# IRQF401RCT6.net
KiCad netlist of a schematic drawn in EAGLE
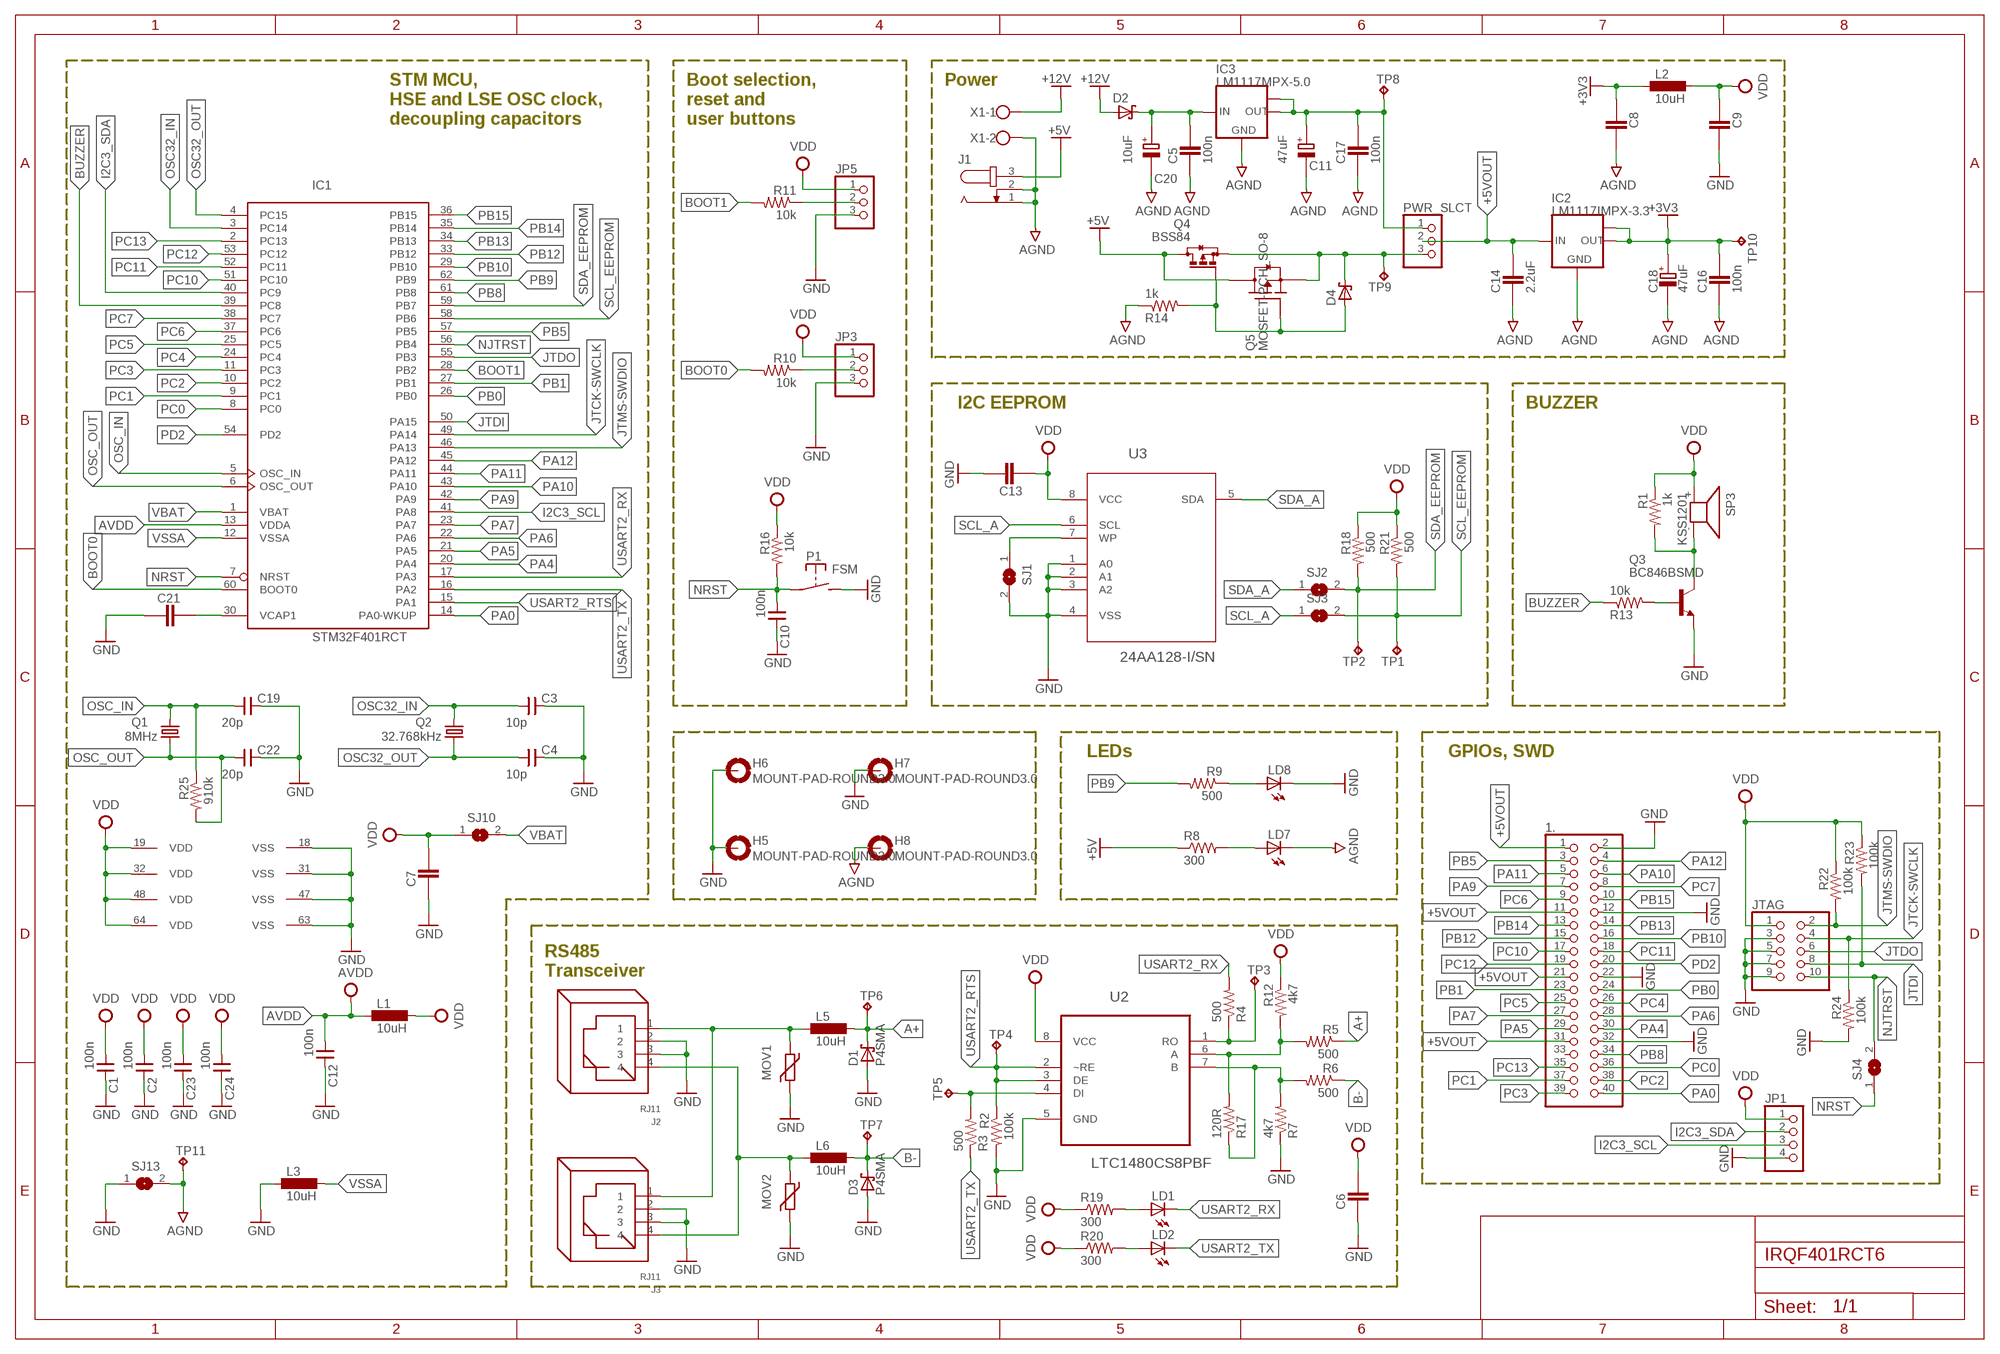
[diagram p0: schematic, sheet 1]

(export (version "E")
  (design (tool "Eeschema 10.0.6"))
  (components
    (comp (ref "1.")
      (value "PINHD-2X20")
      (footprint "eagle-import:2X20")
      (libsource (lib "eagle-import") (part "PINHD-2X20"))
    )
    (comp (ref "C1")
      (value "100n")
      (footprint "eagle-import:0805")
      (libsource (lib "eagle-import") (part "CNP-0805"))
    )
    (comp (ref "C2")
      (value "100n")
      (footprint "eagle-import:0805")
      (libsource (lib "eagle-import") (part "CNP-0805"))
    )
    (comp (ref "C3")
      (value "10p")
      (footprint "eagle-import:0805")
      (libsource (lib "eagle-import") (part "CNP-0805"))
    )
    (comp (ref "C4")
      (value "10p")
      (footprint "eagle-import:0805")
      (libsource (lib "eagle-import") (part "CNP-0805"))
    )
    (comp (ref "C5")
      (value "100n")
      (footprint "eagle-import:CAPC2012X145AN")
      (libsource (lib "eagle-import") (part "CAPACITOR_0805"))
    )
    (comp (ref "C6")
      (value "CAPACITOR_1206")
      (footprint "eagle-import:CAPC3215X168N")
      (libsource (lib "eagle-import") (part "CAPACITOR_1206"))
    )
    (comp (ref "C7")
      (value "CAPACITOR_1206")
      (footprint "eagle-import:CAPC3215X168N")
      (libsource (lib "eagle-import") (part "CAPACITOR_1206"))
    )
    (comp (ref "C8")
      (value "CAPACITOR_1206")
      (footprint "eagle-import:CAPC3215X168N")
      (libsource (lib "eagle-import") (part "CAPACITOR_1206"))
    )
    (comp (ref "C9")
      (value "CAPACITOR_1206")
      (footprint "eagle-import:CAPC3215X168N")
      (libsource (lib "eagle-import") (part "CAPACITOR_1206"))
    )
    (comp (ref "C10")
      (value "100n")
      (footprint "eagle-import:0805")
      (libsource (lib "eagle-import") (part "CNP-0805"))
    )
    (comp (ref "C11")
      (value "47uF")
      (footprint "eagle-import:CAPAE660X540N")
      (libsource (lib "eagle-import") (part "POLARISED_CASE_D"))
    )
    (comp (ref "C12")
      (value "100n")
      (footprint "eagle-import:0805")
      (libsource (lib "eagle-import") (part "CNP-0805"))
    )
    (comp (ref "C13")
      (value "CAPACITOR_1206")
      (footprint "eagle-import:CAPC3215X168N")
      (libsource (lib "eagle-import") (part "CAPACITOR_1206"))
    )
    (comp (ref "C14")
      (value "2.2uF")
      (footprint "eagle-import:CAPC3215X168N")
      (libsource (lib "eagle-import") (part "CAPACITOR_1206"))
    )
    (comp (ref "C16")
      (value "100n")
      (footprint "eagle-import:CAPC2012X145AN")
      (libsource (lib "eagle-import") (part "CAPACITOR_0805"))
    )
    (comp (ref "C17")
      (value "100n")
      (footprint "eagle-import:CAPC2012X145AN")
      (libsource (lib "eagle-import") (part "CAPACITOR_0805"))
    )
    (comp (ref "C18")
      (value "47uF")
      (footprint "eagle-import:CAPAE530X540N")
      (libsource (lib "eagle-import") (part "POLARISED_CASE_C"))
    )
    (comp (ref "C19")
      (value "20p")
      (footprint "eagle-import:0805")
      (libsource (lib "eagle-import") (part "CNP-0805"))
    )
    (comp (ref "C20")
      (value "10uF")
      (footprint "eagle-import:CAPAE430X540N")
      (libsource (lib "eagle-import") (part "POLARISED_CASE_B"))
    )
    (comp (ref "C21")
      (value "CAPACITOR_1206")
      (footprint "eagle-import:CAPC3215X168N")
      (libsource (lib "eagle-import") (part "CAPACITOR_1206"))
    )
    (comp (ref "C22")
      (value "20p")
      (footprint "eagle-import:0805")
      (libsource (lib "eagle-import") (part "CNP-0805"))
    )
    (comp (ref "C23")
      (value "100n")
      (footprint "eagle-import:0805")
      (libsource (lib "eagle-import") (part "CNP-0805"))
    )
    (comp (ref "C24")
      (value "100n")
      (footprint "eagle-import:0805")
      (libsource (lib "eagle-import") (part "CNP-0805"))
    )
    (comp (ref "D1")
      (value "P4SMA")
      (footprint "eagle-import:SMB")
      (libsource (lib "eagle-import") (part "SCHOTTKY-DIODESMD"))
    )
    (comp (ref "D2")
      (value "SCHOTTKY_SMA")
      (footprint "eagle-import:DIOM5326X292N")
      (libsource (lib "eagle-import") (part "SCHOTTKY_SMA"))
    )
    (comp (ref "D3")
      (value "P4SMA")
      (footprint "eagle-import:SMB")
      (libsource (lib "eagle-import") (part "SCHOTTKY-DIODESMD"))
    )
    (comp (ref "D4")
      (value "SCHOTTKY_SMA")
      (footprint "eagle-import:DIOM5326X292N")
      (libsource (lib "eagle-import") (part "SCHOTTKY_SMA"))
    )
    (comp (ref "H5")
      (value "MOUNT-PAD-ROUND3.0")
      (footprint "eagle-import:3,0-PAD")
      (libsource (lib "eagle-import") (part "MOUNT-PAD-ROUND3.0"))
    )
    (comp (ref "H6")
      (value "MOUNT-PAD-ROUND3.0")
      (footprint "eagle-import:3,0-PAD")
      (libsource (lib "eagle-import") (part "MOUNT-PAD-ROUND3.0"))
    )
    (comp (ref "H7")
      (value "MOUNT-PAD-ROUND3.0")
      (footprint "eagle-import:3,0-PAD")
      (libsource (lib "eagle-import") (part "MOUNT-PAD-ROUND3.0"))
    )
    (comp (ref "H8")
      (value "MOUNT-PAD-ROUND3.0")
      (footprint "eagle-import:3,0-PAD")
      (libsource (lib "eagle-import") (part "MOUNT-PAD-ROUND3.0"))
    )
    (comp (ref "IC1")
      (value "STM32F401RCT")
      (footprint "eagle-import:LQFP64")
      (libsource (lib "eagle-import") (part "STM32F401RTC"))
    )
    (comp (ref "IC2")
      (value "LM1117IMPX-3.3")
      (footprint "eagle-import:SOT223")
      (libsource (lib "eagle-import") (part "LM1117IMPX-3.3"))
    )
    (comp (ref "IC3")
      (value "LM1117MPX-5.0")
      (footprint "eagle-import:SOT223")
      (libsource (lib "eagle-import") (part "LM1117MPX-5.0"))
    )
    (comp (ref "J1")
      (value "JACK-PLUG1")
      (footprint "eagle-import:SPC4078")
      (libsource (lib "eagle-import") (part "JACK-PLUG1"))
    )
    (comp (ref "J2")
      (value "RJ11")
      (footprint "eagle-import:RJ11")
      (libsource (lib "eagle-import") (part "RJ11"))
    )
    (comp (ref "J3")
      (value "RJ11")
      (footprint "eagle-import:RJ11")
      (libsource (lib "eagle-import") (part "RJ11"))
    )
    (comp (ref "JP1")
      (value "PINHD-1X4")
      (footprint "eagle-import:1X04")
      (libsource (lib "eagle-import") (part "PINHD-1X4"))
    )
    (comp (ref "JP3")
      (value "PINHD-1X3")
      (footprint "eagle-import:1X03")
      (libsource (lib "eagle-import") (part "PINHD-1X3"))
    )
    (comp (ref "JP5")
      (value "PINHD-1X3")
      (footprint "eagle-import:1X03")
      (libsource (lib "eagle-import") (part "PINHD-1X3"))
    )
    (comp (ref "JTAG")
      (value "PINHD-2X5")
      (footprint "eagle-import:2X05")
      (libsource (lib "eagle-import") (part "PINHD-2X5"))
    )
    (comp (ref "L1")
      (value "10uH")
      (footprint "eagle-import:INDC1608X95N")
      (libsource (lib "eagle-import") (part "INDUCTOR_0603"))
    )
    (comp (ref "L2")
      (value "10uH")
      (footprint "eagle-import:INDC1608X95N")
      (libsource (lib "eagle-import") (part "INDUCTOR_0603"))
    )
    (comp (ref "L3")
      (value "10uH")
      (footprint "eagle-import:INDC1608X95N")
      (libsource (lib "eagle-import") (part "INDUCTOR_0603"))
    )
    (comp (ref "L5")
      (value "10uH")
      (footprint "eagle-import:INDC1608X95N")
      (libsource (lib "eagle-import") (part "INDUCTOR_0603"))
    )
    (comp (ref "L6")
      (value "10uH")
      (footprint "eagle-import:INDC1608X95N")
      (libsource (lib "eagle-import") (part "INDUCTOR_0603"))
    )
    (comp (ref "LD1")
      (value "LEDCHIPLED_0805")
      (footprint "eagle-import:CHIPLED_0805")
      (libsource (lib "eagle-import") (part "LEDCHIPLED_0805"))
    )
    (comp (ref "LD2")
      (value "LEDCHIPLED_0805")
      (footprint "eagle-import:CHIPLED_0805")
      (libsource (lib "eagle-import") (part "LEDCHIPLED_0805"))
    )
    (comp (ref "LD7")
      (value "LEDCHIPLED_0805")
      (footprint "eagle-import:CHIPLED_0805")
      (libsource (lib "eagle-import") (part "LEDCHIPLED_0805"))
    )
    (comp (ref "LD8")
      (value "LEDCHIPLED_0805")
      (footprint "eagle-import:CHIPLED_0805")
      (libsource (lib "eagle-import") (part "LEDCHIPLED_0805"))
    )
    (comp (ref "MOV1")
      (value "VARISTOR_0805")
      (footprint "eagle-import:VARC2012X70N")
      (libsource (lib "eagle-import") (part "VARISTOR_0805"))
    )
    (comp (ref "MOV2")
      (value "VARISTOR_0805")
      (footprint "eagle-import:VARC2012X70N")
      (libsource (lib "eagle-import") (part "VARISTOR_0805"))
    )
    (comp (ref "P1")
      (value "FSM")
      (footprint "eagle-import:FSM")
      (libsource (lib "eagle-import") (part "FSM"))
    )
    (comp (ref "PWR_SLCT")
      (value "PINHD-1X3")
      (footprint "eagle-import:1X03")
      (libsource (lib "eagle-import") (part "PINHD-1X3"))
    )
    (comp (ref "Q1")
      (value "8MHz")
      (footprint "eagle-import:HC49_S")
      (libsource (lib "eagle-import") (part "CRYTALHC49S"))
    )
    (comp (ref "Q2")
      (value "32.768kHz")
      (footprint "eagle-import:TC26H")
      (libsource (lib "eagle-import") (part "CRYTALTC26H"))
    )
    (comp (ref "Q3")
      (value "BC846BSMD")
      (footprint "eagle-import:SOT23")
      (libsource (lib "eagle-import") (part "BC846SMDB"))
    )
    (comp (ref "Q4")
      (value "BSS84")
      (footprint "eagle-import:SOT23")
      (libsource (lib "eagle-import") (part "BSS84"))
    )
    (comp (ref "Q5")
      (value "MOSFET-PCH_SO-8")
      (footprint "eagle-import:SOIC127P600X175-8AN")
      (libsource (lib "eagle-import") (part "MOSFET-PCH_SO-8"))
    )
    (comp (ref "R1")
      (value "1k")
      (footprint "eagle-import:M0805")
      (libsource (lib "eagle-import") (part "R-US_M0805"))
    )
    (comp (ref "R2")
      (value "100k")
      (footprint "eagle-import:M0805")
      (libsource (lib "eagle-import") (part "R-US_M0805"))
    )
    (comp (ref "R3")
      (value "500")
      (footprint "eagle-import:M0805")
      (libsource (lib "eagle-import") (part "R-US_M0805"))
    )
    (comp (ref "R4")
      (value "500")
      (footprint "eagle-import:M0805")
      (libsource (lib "eagle-import") (part "R-US_M0805"))
    )
    (comp (ref "R5")
      (value "500")
      (footprint "eagle-import:M0805")
      (libsource (lib "eagle-import") (part "R-US_M0805"))
    )
    (comp (ref "R6")
      (value "500")
      (footprint "eagle-import:M0805")
      (libsource (lib "eagle-import") (part "R-US_M0805"))
    )
    (comp (ref "R7")
      (value "4k7")
      (footprint "eagle-import:M0805")
      (libsource (lib "eagle-import") (part "R-US_M0805"))
    )
    (comp (ref "R8")
      (value "300")
      (footprint "eagle-import:M0805")
      (libsource (lib "eagle-import") (part "R-US_M0805"))
    )
    (comp (ref "R9")
      (value "500")
      (footprint "eagle-import:M0805")
      (libsource (lib "eagle-import") (part "R-US_M0805"))
    )
    (comp (ref "R10")
      (value "10k")
      (footprint "eagle-import:M0805")
      (libsource (lib "eagle-import") (part "R-US_M0805"))
    )
    (comp (ref "R11")
      (value "10k")
      (footprint "eagle-import:M0805")
      (libsource (lib "eagle-import") (part "R-US_M0805"))
    )
    (comp (ref "R12")
      (value "4k7")
      (footprint "eagle-import:M0805")
      (libsource (lib "eagle-import") (part "R-US_M0805"))
    )
    (comp (ref "R13")
      (value "10k")
      (footprint "eagle-import:M0805")
      (libsource (lib "eagle-import") (part "R-US_M0805"))
    )
    (comp (ref "R14")
      (value "1k")
      (footprint "eagle-import:M0805")
      (libsource (lib "eagle-import") (part "R-US_M0805"))
    )
    (comp (ref "R16")
      (value "10k")
      (footprint "eagle-import:M0805")
      (libsource (lib "eagle-import") (part "R-US_M0805"))
    )
    (comp (ref "R17")
      (value "120R")
      (footprint "eagle-import:M0805")
      (libsource (lib "eagle-import") (part "R-US_M0805"))
    )
    (comp (ref "R18")
      (value "500")
      (footprint "eagle-import:M0805")
      (libsource (lib "eagle-import") (part "R-US_M0805"))
    )
    (comp (ref "R19")
      (value "300")
      (footprint "eagle-import:M0805")
      (libsource (lib "eagle-import") (part "R-US_M0805"))
    )
    (comp (ref "R20")
      (value "300")
      (footprint "eagle-import:M0805")
      (libsource (lib "eagle-import") (part "R-US_M0805"))
    )
    (comp (ref "R21")
      (value "500")
      (footprint "eagle-import:M0805")
      (libsource (lib "eagle-import") (part "R-US_M0805"))
    )
    (comp (ref "R22")
      (value "100k")
      (footprint "eagle-import:M0805")
      (libsource (lib "eagle-import") (part "R-US_M0805"))
    )
    (comp (ref "R23")
      (value "100k")
      (footprint "eagle-import:M0805")
      (libsource (lib "eagle-import") (part "R-US_M0805"))
    )
    (comp (ref "R24")
      (value "100k")
      (footprint "eagle-import:M0805")
      (libsource (lib "eagle-import") (part "R-US_M0805"))
    )
    (comp (ref "R25")
      (value "910k")
      (footprint "eagle-import:M0805")
      (libsource (lib "eagle-import") (part "R-US_M0805"))
    )
    (comp (ref "SJ1") (value "SJ") (footprint "eagle-import:SJ") (libsource (lib "eagle-import") (part "SJ")))
    (comp (ref "SJ2") (value "SJ") (footprint "eagle-import:SJ") (libsource (lib "eagle-import") (part "SJ")))
    (comp (ref "SJ3") (value "SJ") (footprint "eagle-import:SJ") (libsource (lib "eagle-import") (part "SJ")))
    (comp (ref "SJ4") (value "SJ") (footprint "eagle-import:SJ") (libsource (lib "eagle-import") (part "SJ")))
    (comp (ref "SJ10")
      (value "SJ")
      (footprint "eagle-import:SJ")
      (libsource (lib "eagle-import") (part "SJ"))
    )
    (comp (ref "SJ13")
      (value "SJ")
      (footprint "eagle-import:SJ")
      (libsource (lib "eagle-import") (part "SJ"))
    )
    (comp (ref "SP3")
      (value "KSS1201")
      (footprint "eagle-import:KSS1201")
      (libsource (lib "eagle-import") (part "KSS1201"))
    )
    (comp (ref "TP1")
      (value "TPTP10R")
      (footprint "eagle-import:TP10R")
      (libsource (lib "eagle-import") (part "TPTP10R"))
    )
    (comp (ref "TP2")
      (value "TPTP10R")
      (footprint "eagle-import:TP10R")
      (libsource (lib "eagle-import") (part "TPTP10R"))
    )
    (comp (ref "TP3")
      (value "TPTP10R")
      (footprint "eagle-import:TP10R")
      (libsource (lib "eagle-import") (part "TPTP10R"))
    )
    (comp (ref "TP4")
      (value "TPTP10R")
      (footprint "eagle-import:TP10R")
      (libsource (lib "eagle-import") (part "TPTP10R"))
    )
    (comp (ref "TP5")
      (value "TPTP10R")
      (footprint "eagle-import:TP10R")
      (libsource (lib "eagle-import") (part "TPTP10R"))
    )
    (comp (ref "TP6")
      (value "TPTP10R")
      (footprint "eagle-import:TP10R")
      (libsource (lib "eagle-import") (part "TPTP10R"))
    )
    (comp (ref "TP7")
      (value "TPTP10R")
      (footprint "eagle-import:TP10R")
      (libsource (lib "eagle-import") (part "TPTP10R"))
    )
    (comp (ref "TP8")
      (value "TPTP10R")
      (footprint "eagle-import:TP10R")
      (libsource (lib "eagle-import") (part "TPTP10R"))
    )
    (comp (ref "TP9")
      (value "TPTP10R")
      (footprint "eagle-import:TP10R")
      (libsource (lib "eagle-import") (part "TPTP10R"))
    )
    (comp (ref "TP10")
      (value "TPTP10R")
      (footprint "eagle-import:TP10R")
      (libsource (lib "eagle-import") (part "TPTP10R"))
    )
    (comp (ref "TP11")
      (value "TPTP10R")
      (footprint "eagle-import:TP10R")
      (libsource (lib "eagle-import") (part "TPTP10R"))
    )
    (comp (ref "U2")
      (value "LTC1480CS8PBF")
      (footprint "eagle-import:SOIC127P600X175-8N")
      (fields (field (name "MPN") "LTC1480CS8#PBF"))
      (libsource (lib "eagle-import") (part "LTC1480CS8PBF"))
    )
    (comp (ref "U3")
      (value "24AA128-I/SN")
      (footprint "eagle-import:SOIC127P600X175-8N")
      (libsource (lib "eagle-import") (part "24AA128-I/SN"))
    )
    (comp (ref "X1")
      (value "W237-102")
      (footprint "eagle-import:W237-102")
      (libsource (lib "eagle-import") (part "W237-102"))
    )
  )
  (nets
    (net (code "1") (name "+3V3") (class "Default")
      (node (ref "C16") (pin "2") (pinfunction "2_2") (pintype "passive"))
      (node (ref "C18") (pin "+") (pinfunction "+_+") (pintype "passive"))
      (node (ref "C8") (pin "1") (pinfunction "1_1") (pintype "passive"))
      (node (ref "IC2") (pin "2") (pinfunction "OUT_2") (pintype "passive"))
      (node (ref "IC2") (pin "TAB") (pinfunction "OUT1_TAB") (pintype "passive"))
      (node (ref "L2") (pin "1") (pinfunction "1_1") (pintype "passive"))
      (node (ref "TP10") (pin "TP") (pinfunction "TP_TP") (pintype "input"))
    )
    (net (code "2") (name "+5V") (class "Default")
      (node (ref "J1") (pin "3") (pinfunction "3_3") (pintype "passive"))
      (node (ref "Q4") (pin "3") (pinfunction "D_3") (pintype "passive"))
      (node (ref "Q5") (pin "5") (pinfunction "D_5") (pintype "passive"))
      (node (ref "R8") (pin "1") (pinfunction "1_1") (pintype "passive"))
    )
    (net (code "3") (name "+5VOUT") (class "Default")
      (node (ref "1.") (pin "1") (pinfunction "1_1") (pintype "passive"))
      (node (ref "1.") (pin "11") (pinfunction "11_11") (pintype "passive"))
      (node (ref "1.") (pin "21") (pinfunction "21_21") (pintype "passive"))
      (node (ref "1.") (pin "31") (pinfunction "31_31") (pintype "passive"))
      (node (ref "C14") (pin "2") (pinfunction "2_2") (pintype "passive"))
      (node (ref "IC2") (pin "3") (pinfunction "IN_3") (pintype "input"))
      (node (ref "PWR_SLCT") (pin "2") (pinfunction "2_2") (pintype "passive"))
    )
    (net (code "4") (name "+12V") (class "Default")
      (node (ref "D2") (pin "A") (pinfunction "A_A") (pintype "passive"))
      (node (ref "X1") (pin "1") (pinfunction "KL_1") (pintype "passive"))
    )
    (net (code "5") (name "A+") (class "Default")
      (node (ref "D1") (pin "C") (pinfunction "C_C") (pintype "passive"))
      (node (ref "L5") (pin "2") (pinfunction "2_2") (pintype "passive"))
      (node (ref "R5") (pin "1") (pinfunction "1_1") (pintype "passive"))
      (node (ref "TP6") (pin "TP") (pinfunction "TP_TP") (pintype "input"))
    )
    (net (code "6") (name "AGND") (class "Default")
      (node (ref "C11") (pin "-") (pinfunction "-_-") (pintype "passive"))
      (node (ref "C14") (pin "1") (pinfunction "1_1") (pintype "passive"))
      (node (ref "C16") (pin "1") (pinfunction "1_1") (pintype "passive"))
      (node (ref "C17") (pin "1") (pinfunction "1_1") (pintype "passive"))
      (node (ref "C18") (pin "-") (pinfunction "-_-") (pintype "passive"))
      (node (ref "C20") (pin "-") (pinfunction "-_-") (pintype "passive"))
      (node (ref "C5") (pin "1") (pinfunction "1_1") (pintype "passive"))
      (node (ref "C8") (pin "2") (pinfunction "2_2") (pintype "passive"))
      (node (ref "H8") (pin "B3,0") (pinfunction "MOUNT_B3,0") (pintype "passive"))
      (node (ref "IC2") (pin "1") (pinfunction "GND_1") (pintype "input"))
      (node (ref "IC3") (pin "1") (pinfunction "GND_1") (pintype "input"))
      (node (ref "J1") (pin "1") (pinfunction "1_1") (pintype "passive"))
      (node (ref "J1") (pin "2") (pinfunction "2_2") (pintype "passive"))
      (node (ref "LD7") (pin "C") (pinfunction "C_C") (pintype "passive"))
      (node (ref "R14") (pin "1") (pinfunction "1_1") (pintype "passive"))
      (node (ref "SJ13") (pin "2") (pinfunction "2_2") (pintype "passive"))
      (node (ref "TP11") (pin "TP") (pinfunction "TP_TP") (pintype "input"))
      (node (ref "X1") (pin "2") (pinfunction "KL_2") (pintype "passive"))
    )
    (net (code "7") (name "AVDD") (class "Default")
      (node (ref "C12") (pin "1") (pinfunction "1_1") (pintype "passive"))
      (node (ref "IC1") (pin "13") (pinfunction "VDDA_13") (pintype "power_in"))
      (node (ref "L1") (pin "1") (pinfunction "1_1") (pintype "passive"))
    )
    (net (code "8") (name "B-") (class "Default")
      (node (ref "D3") (pin "C") (pinfunction "C_C") (pintype "passive"))
      (node (ref "L6") (pin "2") (pinfunction "2_2") (pintype "passive"))
      (node (ref "R6") (pin "1") (pinfunction "1_1") (pintype "passive"))
      (node (ref "TP7") (pin "TP") (pinfunction "TP_TP") (pintype "input"))
    )
    (net (code "9") (name "BOOT0") (class "Default")
      (node (ref "IC1") (pin "60") (pinfunction "BOOT0_60") (pintype "input"))
      (node (ref "R10") (pin "2") (pinfunction "2_2") (pintype "passive"))
    )
    (net (code "10") (name "BOOT1") (class "Default")
      (node (ref "IC1") (pin "28") (pinfunction "PB2_28") (pintype "bidirectional"))
      (node (ref "R11") (pin "2") (pinfunction "2_2") (pintype "passive"))
    )
    (net (code "11") (name "BUZZER") (class "Default")
      (node (ref "IC1") (pin "39") (pinfunction "PC8_39") (pintype "bidirectional"))
      (node (ref "R13") (pin "1") (pinfunction "1_1") (pintype "passive"))
    )
    (net (code "12") (name "GND") (class "Default")
      (node (ref "1.") (pin "12") (pinfunction "12_12") (pintype "passive"))
      (node (ref "1.") (pin "2") (pinfunction "2_2") (pintype "passive"))
      (node (ref "1.") (pin "22") (pinfunction "22_22") (pintype "passive"))
      (node (ref "1.") (pin "32") (pinfunction "32_32") (pintype "passive"))
      (node (ref "C1") (pin "2") (pinfunction "2_2") (pintype "passive"))
      (node (ref "C10") (pin "2") (pinfunction "2_2") (pintype "passive"))
      (node (ref "C12") (pin "2") (pinfunction "2_2") (pintype "passive"))
      (node (ref "C13") (pin "2") (pinfunction "2_2") (pintype "passive"))
      (node (ref "C19") (pin "2") (pinfunction "2_2") (pintype "passive"))
      (node (ref "C2") (pin "2") (pinfunction "2_2") (pintype "passive"))
      (node (ref "C21") (pin "1") (pinfunction "1_1") (pintype "passive"))
      (node (ref "C22") (pin "2") (pinfunction "2_2") (pintype "passive"))
      (node (ref "C23") (pin "2") (pinfunction "2_2") (pintype "passive"))
      (node (ref "C24") (pin "2") (pinfunction "2_2") (pintype "passive"))
      (node (ref "C3") (pin "2") (pinfunction "2_2") (pintype "passive"))
      (node (ref "C4") (pin "2") (pinfunction "2_2") (pintype "passive"))
      (node (ref "C6") (pin "1") (pinfunction "1_1") (pintype "passive"))
      (node (ref "C7") (pin "1") (pinfunction "1_1") (pintype "passive"))
      (node (ref "C9") (pin "2") (pinfunction "2_2") (pintype "passive"))
      (node (ref "D1") (pin "A") (pinfunction "A_A") (pintype "passive"))
      (node (ref "D3") (pin "A") (pinfunction "A_A") (pintype "passive"))
      (node (ref "H5") (pin "B3,0") (pinfunction "MOUNT_B3,0") (pintype "passive"))
      (node (ref "H6") (pin "B3,0") (pinfunction "MOUNT_B3,0") (pintype "passive"))
      (node (ref "H7") (pin "B3,0") (pinfunction "MOUNT_B3,0") (pintype "passive"))
      (node (ref "IC1") (pin "18") (pinfunction "VSS_18") (pintype "power_in"))
      (node (ref "IC1") (pin "31") (pinfunction "VSS_31") (pintype "power_in"))
      (node (ref "IC1") (pin "47") (pinfunction "VSS_47") (pintype "power_in"))
      (node (ref "IC1") (pin "63") (pinfunction "VSS_63") (pintype "power_in"))
      (node (ref "J2") (pin "2") (pinfunction "2_2") (pintype "bidirectional"))
      (node (ref "J2") (pin "3") (pinfunction "3_3") (pintype "bidirectional"))
      (node (ref "J3") (pin "2") (pinfunction "2_2") (pintype "bidirectional"))
      (node (ref "J3") (pin "3") (pinfunction "3_3") (pintype "bidirectional"))
      (node (ref "JP1") (pin "4") (pinfunction "4_4") (pintype "passive"))
      (node (ref "JP3") (pin "3") (pinfunction "3_3") (pintype "passive"))
      (node (ref "JP5") (pin "3") (pinfunction "3_3") (pintype "passive"))
      (node (ref "JTAG") (pin "3") (pinfunction "3_3") (pintype "passive"))
      (node (ref "JTAG") (pin "5") (pinfunction "5_5") (pintype "passive"))
      (node (ref "JTAG") (pin "7") (pinfunction "7_7") (pintype "passive"))
      (node (ref "JTAG") (pin "9") (pinfunction "9_9") (pintype "passive"))
      (node (ref "L3") (pin "1") (pinfunction "1_1") (pintype "passive"))
      (node (ref "LD8") (pin "C") (pinfunction "C_C") (pintype "passive"))
      (node (ref "MOV1") (pin "1") (pinfunction "1_1") (pintype "passive"))
      (node (ref "MOV2") (pin "1") (pinfunction "1_1") (pintype "passive"))
      (node (ref "P1") (pin "P$2") (pinfunction "S_P$2") (pintype "passive"))
      (node (ref "Q3") (pin "2") (pinfunction "E_2") (pintype "passive"))
      (node (ref "R2") (pin "2") (pinfunction "2_2") (pintype "passive"))
      (node (ref "R24") (pin "2") (pinfunction "2_2") (pintype "passive"))
      (node (ref "R7") (pin "1") (pinfunction "1_1") (pintype "passive"))
      (node (ref "SJ1") (pin "2") (pinfunction "2_2") (pintype "passive"))
      (node (ref "SJ13") (pin "1") (pinfunction "1_1") (pintype "passive"))
      (node (ref "U2") (pin "5") (pinfunction "GND_5") (pintype "passive"))
      (node (ref "U3") (pin "1") (pinfunction "A0_1") (pintype "input"))
      (node (ref "U3") (pin "2") (pinfunction "A1_2") (pintype "input"))
      (node (ref "U3") (pin "3") (pinfunction "A2_3") (pintype "input"))
      (node (ref "U3") (pin "4") (pinfunction "VSS_4") (pintype "power_in"))
    )
    (net (code "13") (name "I2C3_SCL") (class "Default")
      (node (ref "IC1") (pin "41") (pinfunction "PA8_41") (pintype "bidirectional"))
      (node (ref "JP1") (pin "3") (pinfunction "3_3") (pintype "passive"))
    )
    (net (code "14") (name "I2C3_SDA") (class "Default")
      (node (ref "IC1") (pin "40") (pinfunction "PC9_40") (pintype "bidirectional"))
      (node (ref "JP1") (pin "2") (pinfunction "2_2") (pintype "passive"))
    )
    (net (code "15") (name "JTCK-SWCLK") (class "Default")
      (node (ref "IC1") (pin "49") (pinfunction "PA14_49") (pintype "bidirectional"))
      (node (ref "JTAG") (pin "4") (pinfunction "4_4") (pintype "passive"))
      (node (ref "R24") (pin "1") (pinfunction "1_1") (pintype "passive"))
    )
    (net (code "16") (name "JTDI") (class "Default")
      (node (ref "IC1") (pin "50") (pinfunction "PA15_50") (pintype "bidirectional"))
      (node (ref "JTAG") (pin "8") (pinfunction "8_8") (pintype "passive"))
      (node (ref "R23") (pin "2") (pinfunction "2_2") (pintype "passive"))
    )
    (net (code "17") (name "JTDO") (class "Default")
      (node (ref "IC1") (pin "55") (pinfunction "PB3_55") (pintype "bidirectional"))
      (node (ref "JTAG") (pin "6") (pinfunction "6_6") (pintype "passive"))
    )
    (net (code "18") (name "JTMS-SWDIO") (class "Default")
      (node (ref "IC1") (pin "46") (pinfunction "PA13_46") (pintype "bidirectional"))
      (node (ref "JTAG") (pin "2") (pinfunction "2_2") (pintype "passive"))
      (node (ref "R22") (pin "2") (pinfunction "2_2") (pintype "passive"))
    )
    (net (code "19") (name "NJTRST") (class "Default")
      (node (ref "IC1") (pin "56") (pinfunction "PB4_56") (pintype "bidirectional"))
      (node (ref "JTAG") (pin "10") (pinfunction "10_10") (pintype "passive"))
      (node (ref "SJ4") (pin "2") (pinfunction "2_2") (pintype "passive"))
    )
    (net (code "20") (name "NRST") (class "Default")
      (node (ref "C10") (pin "1") (pinfunction "1_1") (pintype "passive"))
      (node (ref "IC1") (pin "7") (pinfunction "NRST_7") (pintype "bidirectional"))
      (node (ref "P1") (pin "P$1") (pinfunction "P_P$1") (pintype "passive"))
      (node (ref "R16") (pin "2") (pinfunction "2_2") (pintype "passive"))
      (node (ref "SJ4") (pin "1") (pinfunction "1_1") (pintype "passive"))
    )
    (net (code "21") (name "Net-(IC1A-VCAP1)") (class "Default")
      (node (ref "C21") (pin "2") (pinfunction "2_2") (pintype "passive"))
      (node (ref "IC1") (pin "30") (pinfunction "VCAP1_30") (pintype "power_in"))
    )
    (net (code "22") (name "Net-(IC3-IN)") (class "Default")
      (node (ref "C20") (pin "+") (pinfunction "+_+") (pintype "passive"))
      (node (ref "C5") (pin "2") (pinfunction "2_2") (pintype "passive"))
      (node (ref "D2") (pin "K") (pinfunction "K_K") (pintype "passive"))
      (node (ref "IC3") (pin "3") (pinfunction "IN_3") (pintype "input"))
    )
    (net (code "23") (name "Net-(IC3-OUT)") (class "Default")
      (node (ref "C11") (pin "+") (pinfunction "+_+") (pintype "passive"))
      (node (ref "C17") (pin "2") (pinfunction "2_2") (pintype "passive"))
      (node (ref "IC3") (pin "2") (pinfunction "OUT_2") (pintype "passive"))
      (node (ref "IC3") (pin "TAB") (pinfunction "OUT1_TAB") (pintype "passive"))
      (node (ref "PWR_SLCT") (pin "1") (pinfunction "1_1") (pintype "passive"))
      (node (ref "TP8") (pin "TP") (pinfunction "TP_TP") (pintype "input"))
    )
    (net (code "24") (name "Net-(J2-Pad1)") (class "Default")
      (node (ref "J2") (pin "1") (pinfunction "1_1") (pintype "bidirectional"))
      (node (ref "J3") (pin "1") (pinfunction "1_1") (pintype "bidirectional"))
      (node (ref "L5") (pin "1") (pinfunction "1_1") (pintype "passive"))
      (node (ref "MOV1") (pin "2") (pinfunction "2_2") (pintype "passive"))
    )
    (net (code "25") (name "Net-(J2-Pad4)") (class "Default")
      (node (ref "J2") (pin "4") (pinfunction "4_4") (pintype "bidirectional"))
      (node (ref "J3") (pin "4") (pinfunction "4_4") (pintype "bidirectional"))
      (node (ref "L6") (pin "1") (pinfunction "1_1") (pintype "passive"))
      (node (ref "MOV2") (pin "2") (pinfunction "2_2") (pintype "passive"))
    )
    (net (code "26") (name "Net-(JP3-Pad2)") (class "Default")
      (node (ref "JP3") (pin "2") (pinfunction "2_2") (pintype "passive"))
      (node (ref "R10") (pin "1") (pinfunction "1_1") (pintype "passive"))
    )
    (net (code "27") (name "Net-(JP5-Pad2)") (class "Default")
      (node (ref "JP5") (pin "2") (pinfunction "2_2") (pintype "passive"))
      (node (ref "R11") (pin "1") (pinfunction "1_1") (pintype "passive"))
    )
    (net (code "28") (name "Net-(LD1-PadA)") (class "Default")
      (node (ref "LD1") (pin "A") (pinfunction "A_A") (pintype "passive"))
      (node (ref "R19") (pin "2") (pinfunction "2_2") (pintype "passive"))
    )
    (net (code "29") (name "Net-(LD2-PadA)") (class "Default")
      (node (ref "LD2") (pin "A") (pinfunction "A_A") (pintype "passive"))
      (node (ref "R20") (pin "2") (pinfunction "2_2") (pintype "passive"))
    )
    (net (code "30") (name "Net-(LD7-PadA)") (class "Default")
      (node (ref "LD7") (pin "A") (pinfunction "A_A") (pintype "passive"))
      (node (ref "R8") (pin "2") (pinfunction "2_2") (pintype "passive"))
    )
    (net (code "31") (name "Net-(LD8-PadA)") (class "Default")
      (node (ref "LD8") (pin "A") (pinfunction "A_A") (pintype "passive"))
      (node (ref "R9") (pin "1") (pinfunction "1_1") (pintype "passive"))
    )
    (net (code "32") (name "Net-(Q3-B)") (class "Default")
      (node (ref "Q3") (pin "1") (pinfunction "B_1") (pintype "passive"))
      (node (ref "R13") (pin "2") (pinfunction "2_2") (pintype "passive"))
    )
    (net (code "33") (name "Net-(Q3-C)") (class "Default")
      (node (ref "Q3") (pin "3") (pinfunction "C_3") (pintype "passive"))
      (node (ref "R1") (pin "2") (pinfunction "2_2") (pintype "passive"))
      (node (ref "SP3") (pin "-") (pinfunction "2_-") (pintype "passive"))
    )
    (net (code "34") (name "Net-(Q4-G)") (class "Default")
      (node (ref "D4") (pin "A") (pinfunction "A_A") (pintype "passive"))
      (node (ref "Q4") (pin "1") (pinfunction "G_1") (pintype "passive"))
      (node (ref "Q5") (pin "4") (pinfunction "G_4") (pintype "passive"))
      (node (ref "R14") (pin "2") (pinfunction "2_2") (pintype "passive"))
    )
    (net (code "35") (name "Net-(Q4-S)") (class "Default")
      (node (ref "D4") (pin "K") (pinfunction "K_K") (pintype "passive"))
      (node (ref "PWR_SLCT") (pin "3") (pinfunction "3_3") (pintype "passive"))
      (node (ref "Q4") (pin "2") (pinfunction "S_2") (pintype "passive"))
      (node (ref "Q5") (pin "1") (pinfunction "S_1") (pintype "passive"))
      (node (ref "TP9") (pin "TP") (pinfunction "TP_TP") (pintype "input"))
    )
    (net (code "36") (name "Net-(U2-A)") (class "Default")
      (node (ref "R12") (pin "2") (pinfunction "2_2") (pintype "passive"))
      (node (ref "R17") (pin "2") (pinfunction "2_2") (pintype "passive"))
      (node (ref "R5") (pin "2") (pinfunction "2_2") (pintype "passive"))
      (node (ref "U2") (pin "6") (pinfunction "A_6") (pintype "bidirectional"))
    )
    (net (code "37") (name "Net-(U2-B)") (class "Default")
      (node (ref "R17") (pin "1") (pinfunction "1_1") (pintype "passive"))
      (node (ref "R6") (pin "2") (pinfunction "2_2") (pintype "passive"))
      (node (ref "R7") (pin "2") (pinfunction "2_2") (pintype "passive"))
      (node (ref "U2") (pin "7") (pinfunction "B_7") (pintype "bidirectional"))
    )
    (net (code "38") (name "Net-(U2-DI)") (class "Default")
      (node (ref "R3") (pin "2") (pinfunction "2_2") (pintype "passive"))
      (node (ref "TP5") (pin "TP") (pinfunction "TP_TP") (pintype "input"))
      (node (ref "U2") (pin "4") (pinfunction "DI_4") (pintype "input"))
    )
    (net (code "39") (name "Net-(U2-RO)") (class "Default")
      (node (ref "R4") (pin "1") (pinfunction "1_1") (pintype "passive"))
      (node (ref "TP3") (pin "TP") (pinfunction "TP_TP") (pintype "input"))
      (node (ref "U2") (pin "1") (pinfunction "RO_1") (pintype "output"))
    )
    (net (code "40") (name "Net-(U3-WP)") (class "Default")
      (node (ref "SJ1") (pin "1") (pinfunction "1_1") (pintype "passive"))
      (node (ref "U3") (pin "7") (pinfunction "WP_7") (pintype "input"))
    )
    (net (code "41") (name "OSC32_IN") (class "Default")
      (node (ref "C3") (pin "1") (pinfunction "1_1") (pintype "passive"))
      (node (ref "IC1") (pin "3") (pinfunction "PC14_3") (pintype "bidirectional"))
      (node (ref "Q2") (pin "2") (pinfunction "2_2") (pintype "passive"))
    )
    (net (code "42") (name "OSC32_OUT") (class "Default")
      (node (ref "C4") (pin "1") (pinfunction "1_1") (pintype "passive"))
      (node (ref "IC1") (pin "4") (pinfunction "PC15_4") (pintype "bidirectional"))
      (node (ref "Q2") (pin "1") (pinfunction "1_1") (pintype "passive"))
    )
    (net (code "43") (name "OSC_IN") (class "Default")
      (node (ref "C19") (pin "1") (pinfunction "1_1") (pintype "passive"))
      (node (ref "IC1") (pin "5") (pinfunction "OSC_IN_5") (pintype "bidirectional"))
      (node (ref "Q1") (pin "2") (pinfunction "2_2") (pintype "passive"))
      (node (ref "R25") (pin "1") (pinfunction "1_1") (pintype "passive"))
    )
    (net (code "44") (name "OSC_OUT") (class "Default")
      (node (ref "C22") (pin "1") (pinfunction "1_1") (pintype "passive"))
      (node (ref "IC1") (pin "6") (pinfunction "OSC_OUT_6") (pintype "bidirectional"))
      (node (ref "Q1") (pin "1") (pinfunction "1_1") (pintype "passive"))
      (node (ref "R25") (pin "2") (pinfunction "2_2") (pintype "passive"))
    )
    (net (code "45") (name "PA0") (class "Default")
      (node (ref "1.") (pin "40") (pinfunction "40_40") (pintype "passive"))
      (node (ref "IC1") (pin "14") (pinfunction "PA0-WKUP_14") (pintype "bidirectional"))
    )
    (net (code "46") (name "PA4") (class "Default")
      (node (ref "1.") (pin "30") (pinfunction "30_30") (pintype "passive"))
      (node (ref "IC1") (pin "20") (pinfunction "PA4_20") (pintype "bidirectional"))
    )
    (net (code "47") (name "PA5") (class "Default")
      (node (ref "1.") (pin "29") (pinfunction "29_29") (pintype "passive"))
      (node (ref "IC1") (pin "21") (pinfunction "PA5_21") (pintype "bidirectional"))
    )
    (net (code "48") (name "PA6") (class "Default")
      (node (ref "1.") (pin "28") (pinfunction "28_28") (pintype "passive"))
      (node (ref "IC1") (pin "22") (pinfunction "PA6_22") (pintype "bidirectional"))
    )
    (net (code "49") (name "PA7") (class "Default")
      (node (ref "1.") (pin "27") (pinfunction "27_27") (pintype "passive"))
      (node (ref "IC1") (pin "23") (pinfunction "PA7_23") (pintype "bidirectional"))
    )
    (net (code "50") (name "PA9") (class "Default")
      (node (ref "1.") (pin "7") (pinfunction "7_7") (pintype "passive"))
      (node (ref "IC1") (pin "42") (pinfunction "PA9_42") (pintype "bidirectional"))
    )
    (net (code "51") (name "PA10") (class "Default")
      (node (ref "1.") (pin "6") (pinfunction "6_6") (pintype "passive"))
      (node (ref "IC1") (pin "43") (pinfunction "PA10_43") (pintype "bidirectional"))
    )
    (net (code "52") (name "PA11") (class "Default")
      (node (ref "1.") (pin "5") (pinfunction "5_5") (pintype "passive"))
      (node (ref "IC1") (pin "44") (pinfunction "PA11_44") (pintype "bidirectional"))
    )
    (net (code "53") (name "PA12") (class "Default")
      (node (ref "1.") (pin "4") (pinfunction "4_4") (pintype "passive"))
      (node (ref "IC1") (pin "45") (pinfunction "PA12_45") (pintype "bidirectional"))
    )
    (net (code "54") (name "PB0") (class "Default")
      (node (ref "1.") (pin "24") (pinfunction "24_24") (pintype "passive"))
      (node (ref "IC1") (pin "26") (pinfunction "PB0_26") (pintype "bidirectional"))
    )
    (net (code "55") (name "PB1") (class "Default")
      (node (ref "1.") (pin "23") (pinfunction "23_23") (pintype "passive"))
      (node (ref "IC1") (pin "27") (pinfunction "PB1_27") (pintype "bidirectional"))
    )
    (net (code "56") (name "PB5") (class "Default")
      (node (ref "1.") (pin "3") (pinfunction "3_3") (pintype "passive"))
      (node (ref "IC1") (pin "57") (pinfunction "PB5_57") (pintype "bidirectional"))
    )
    (net (code "57") (name "PB8") (class "Default")
      (node (ref "1.") (pin "34") (pinfunction "34_34") (pintype "passive"))
      (node (ref "IC1") (pin "61") (pinfunction "PB8_61") (pintype "bidirectional"))
    )
    (net (code "58") (name "PB9") (class "Default")
      (node (ref "IC1") (pin "62") (pinfunction "PB9_62") (pintype "bidirectional"))
      (node (ref "R9") (pin "2") (pinfunction "2_2") (pintype "passive"))
    )
    (net (code "59") (name "PB10") (class "Default")
      (node (ref "1.") (pin "16") (pinfunction "16_16") (pintype "passive"))
      (node (ref "IC1") (pin "29") (pinfunction "PB10_29") (pintype "bidirectional"))
    )
    (net (code "60") (name "PB12") (class "Default")
      (node (ref "1.") (pin "15") (pinfunction "15_15") (pintype "passive"))
      (node (ref "IC1") (pin "33") (pinfunction "PB12_33") (pintype "bidirectional"))
    )
    (net (code "61") (name "PB13") (class "Default")
      (node (ref "1.") (pin "14") (pinfunction "14_14") (pintype "passive"))
      (node (ref "IC1") (pin "34") (pinfunction "PB13_34") (pintype "bidirectional"))
    )
    (net (code "62") (name "PB14") (class "Default")
      (node (ref "1.") (pin "13") (pinfunction "13_13") (pintype "passive"))
      (node (ref "IC1") (pin "35") (pinfunction "PB14_35") (pintype "bidirectional"))
    )
    (net (code "63") (name "PB15") (class "Default")
      (node (ref "1.") (pin "10") (pinfunction "10_10") (pintype "passive"))
      (node (ref "IC1") (pin "36") (pinfunction "PB15_36") (pintype "bidirectional"))
    )
    (net (code "64") (name "PC0") (class "Default")
      (node (ref "1.") (pin "36") (pinfunction "36_36") (pintype "passive"))
      (node (ref "IC1") (pin "8") (pinfunction "PC0_8") (pintype "bidirectional"))
    )
    (net (code "65") (name "PC1") (class "Default")
      (node (ref "1.") (pin "37") (pinfunction "37_37") (pintype "passive"))
      (node (ref "IC1") (pin "9") (pinfunction "PC1_9") (pintype "bidirectional"))
    )
    (net (code "66") (name "PC2") (class "Default")
      (node (ref "1.") (pin "38") (pinfunction "38_38") (pintype "passive"))
      (node (ref "IC1") (pin "10") (pinfunction "PC2_10") (pintype "bidirectional"))
    )
    (net (code "67") (name "PC3") (class "Default")
      (node (ref "1.") (pin "39") (pinfunction "39_39") (pintype "passive"))
      (node (ref "IC1") (pin "11") (pinfunction "PC3_11") (pintype "bidirectional"))
    )
    (net (code "68") (name "PC4") (class "Default")
      (node (ref "1.") (pin "26") (pinfunction "26_26") (pintype "passive"))
      (node (ref "IC1") (pin "24") (pinfunction "PC4_24") (pintype "bidirectional"))
    )
    (net (code "69") (name "PC5") (class "Default")
      (node (ref "1.") (pin "25") (pinfunction "25_25") (pintype "passive"))
      (node (ref "IC1") (pin "25") (pinfunction "PC5_25") (pintype "bidirectional"))
    )
    (net (code "70") (name "PC6") (class "Default")
      (node (ref "1.") (pin "9") (pinfunction "9_9") (pintype "passive"))
      (node (ref "IC1") (pin "37") (pinfunction "PC6_37") (pintype "bidirectional"))
    )
    (net (code "71") (name "PC7") (class "Default")
      (node (ref "1.") (pin "8") (pinfunction "8_8") (pintype "passive"))
      (node (ref "IC1") (pin "38") (pinfunction "PC7_38") (pintype "bidirectional"))
    )
    (net (code "72") (name "PC10") (class "Default")
      (node (ref "1.") (pin "17") (pinfunction "17_17") (pintype "passive"))
      (node (ref "IC1") (pin "51") (pinfunction "PC10_51") (pintype "bidirectional"))
    )
    (net (code "73") (name "PC11") (class "Default")
      (node (ref "1.") (pin "18") (pinfunction "18_18") (pintype "passive"))
      (node (ref "IC1") (pin "52") (pinfunction "PC11_52") (pintype "bidirectional"))
    )
    (net (code "74") (name "PC12") (class "Default")
      (node (ref "1.") (pin "19") (pinfunction "19_19") (pintype "passive"))
      (node (ref "IC1") (pin "53") (pinfunction "PC12_53") (pintype "bidirectional"))
    )
    (net (code "75") (name "PC13") (class "Default")
      (node (ref "1.") (pin "35") (pinfunction "35_35") (pintype "passive"))
      (node (ref "IC1") (pin "2") (pinfunction "PC13_2") (pintype "bidirectional"))
    )
    (net (code "76") (name "PD2") (class "Default")
      (node (ref "1.") (pin "20") (pinfunction "20_20") (pintype "passive"))
      (node (ref "IC1") (pin "54") (pinfunction "PD2_54") (pintype "bidirectional"))
    )
    (net (code "77") (name "SCL_A") (class "Default")
      (node (ref "SJ3") (pin "1") (pinfunction "1_1") (pintype "passive"))
      (node (ref "U3") (pin "6") (pinfunction "SCL_6") (pintype "input"))
    )
    (net (code "78") (name "SCL_EEPROM") (class "Default")
      (node (ref "IC1") (pin "58") (pinfunction "PB6_58") (pintype "bidirectional"))
      (node (ref "R21") (pin "2") (pinfunction "2_2") (pintype "passive"))
      (node (ref "SJ3") (pin "2") (pinfunction "2_2") (pintype "passive"))
      (node (ref "TP1") (pin "TP") (pinfunction "TP_TP") (pintype "input"))
    )
    (net (code "79") (name "SDA_A") (class "Default")
      (node (ref "SJ2") (pin "1") (pinfunction "1_1") (pintype "passive"))
      (node (ref "U3") (pin "5") (pinfunction "SDA_5") (pintype "bidirectional"))
    )
    (net (code "80") (name "SDA_EEPROM") (class "Default")
      (node (ref "IC1") (pin "59") (pinfunction "PB7_59") (pintype "bidirectional"))
      (node (ref "R18") (pin "2") (pinfunction "2_2") (pintype "passive"))
      (node (ref "SJ2") (pin "2") (pinfunction "2_2") (pintype "passive"))
      (node (ref "TP2") (pin "TP") (pinfunction "TP_TP") (pintype "input"))
    )
    (net (code "81") (name "USART2_RTS") (class "Default")
      (node (ref "IC1") (pin "15") (pinfunction "PA1_15") (pintype "bidirectional"))
      (node (ref "R2") (pin "1") (pinfunction "1_1") (pintype "passive"))
      (node (ref "TP4") (pin "TP") (pinfunction "TP_TP") (pintype "input"))
      (node (ref "U2") (pin "2") (pinfunction "~{RE}_2") (pintype "input"))
      (node (ref "U2") (pin "3") (pinfunction "DE_3") (pintype "input"))
    )
    (net (code "82") (name "USART2_RX") (class "Default")
      (node (ref "IC1") (pin "17") (pinfunction "PA3_17") (pintype "bidirectional"))
      (node (ref "LD1") (pin "C") (pinfunction "C_C") (pintype "passive"))
      (node (ref "R4") (pin "2") (pinfunction "2_2") (pintype "passive"))
    )
    (net (code "83") (name "USART2_TX") (class "Default")
      (node (ref "IC1") (pin "16") (pinfunction "PA2_16") (pintype "bidirectional"))
      (node (ref "LD2") (pin "C") (pinfunction "C_C") (pintype "passive"))
      (node (ref "R3") (pin "1") (pinfunction "1_1") (pintype "passive"))
    )
    (net (code "84") (name "VBAT") (class "Default")
      (node (ref "IC1") (pin "1") (pinfunction "VBAT_1") (pintype "power_in"))
      (node (ref "SJ10") (pin "2") (pinfunction "2_2") (pintype "passive"))
    )
    (net (code "85") (name "VDD") (class "Default")
      (node (ref "C1") (pin "1") (pinfunction "1_1") (pintype "passive"))
      (node (ref "C13") (pin "1") (pinfunction "1_1") (pintype "passive"))
      (node (ref "C2") (pin "1") (pinfunction "1_1") (pintype "passive"))
      (node (ref "C23") (pin "1") (pinfunction "1_1") (pintype "passive"))
      (node (ref "C24") (pin "1") (pinfunction "1_1") (pintype "passive"))
      (node (ref "C6") (pin "2") (pinfunction "2_2") (pintype "passive"))
      (node (ref "C7") (pin "2") (pinfunction "2_2") (pintype "passive"))
      (node (ref "C9") (pin "1") (pinfunction "1_1") (pintype "passive"))
      (node (ref "IC1") (pin "19") (pinfunction "VDD_19") (pintype "power_in"))
      (node (ref "IC1") (pin "32") (pinfunction "VDD_32") (pintype "power_in"))
      (node (ref "IC1") (pin "48") (pinfunction "VDD_48") (pintype "power_in"))
      (node (ref "IC1") (pin "64") (pinfunction "VDD_64") (pintype "power_in"))
      (node (ref "JP1") (pin "1") (pinfunction "1_1") (pintype "passive"))
      (node (ref "JP3") (pin "1") (pinfunction "1_1") (pintype "passive"))
      (node (ref "JP5") (pin "1") (pinfunction "1_1") (pintype "passive"))
      (node (ref "JTAG") (pin "1") (pinfunction "1_1") (pintype "passive"))
      (node (ref "L1") (pin "2") (pinfunction "2_2") (pintype "passive"))
      (node (ref "L2") (pin "2") (pinfunction "2_2") (pintype "passive"))
      (node (ref "R1") (pin "1") (pinfunction "1_1") (pintype "passive"))
      (node (ref "R12") (pin "1") (pinfunction "1_1") (pintype "passive"))
      (node (ref "R16") (pin "1") (pinfunction "1_1") (pintype "passive"))
      (node (ref "R18") (pin "1") (pinfunction "1_1") (pintype "passive"))
      (node (ref "R19") (pin "1") (pinfunction "1_1") (pintype "passive"))
      (node (ref "R20") (pin "1") (pinfunction "1_1") (pintype "passive"))
      (node (ref "R21") (pin "1") (pinfunction "1_1") (pintype "passive"))
      (node (ref "R22") (pin "1") (pinfunction "1_1") (pintype "passive"))
      (node (ref "R23") (pin "1") (pinfunction "1_1") (pintype "passive"))
      (node (ref "SJ10") (pin "1") (pinfunction "1_1") (pintype "passive"))
      (node (ref "SP3") (pin "+") (pinfunction "1_+") (pintype "passive"))
      (node (ref "U2") (pin "8") (pinfunction "VCC_8") (pintype "power_in"))
      (node (ref "U3") (pin "8") (pinfunction "VCC_8") (pintype "power_in"))
    )
    (net (code "86") (name "VSSA") (class "Default")
      (node (ref "IC1") (pin "12") (pinfunction "VSSA_12") (pintype "power_in"))
      (node (ref "L3") (pin "2") (pinfunction "2_2") (pintype "passive"))
    )
    (net (code "87") (name "unconnected-(1.-Pad33)") (class "Default")
      (node (ref "1.") (pin "33") (pinfunction "33_33") (pintype "passive"))
    )
  )
)
